# LEDs.net
KiCad netlist of a schematic drawn in Altium Designer
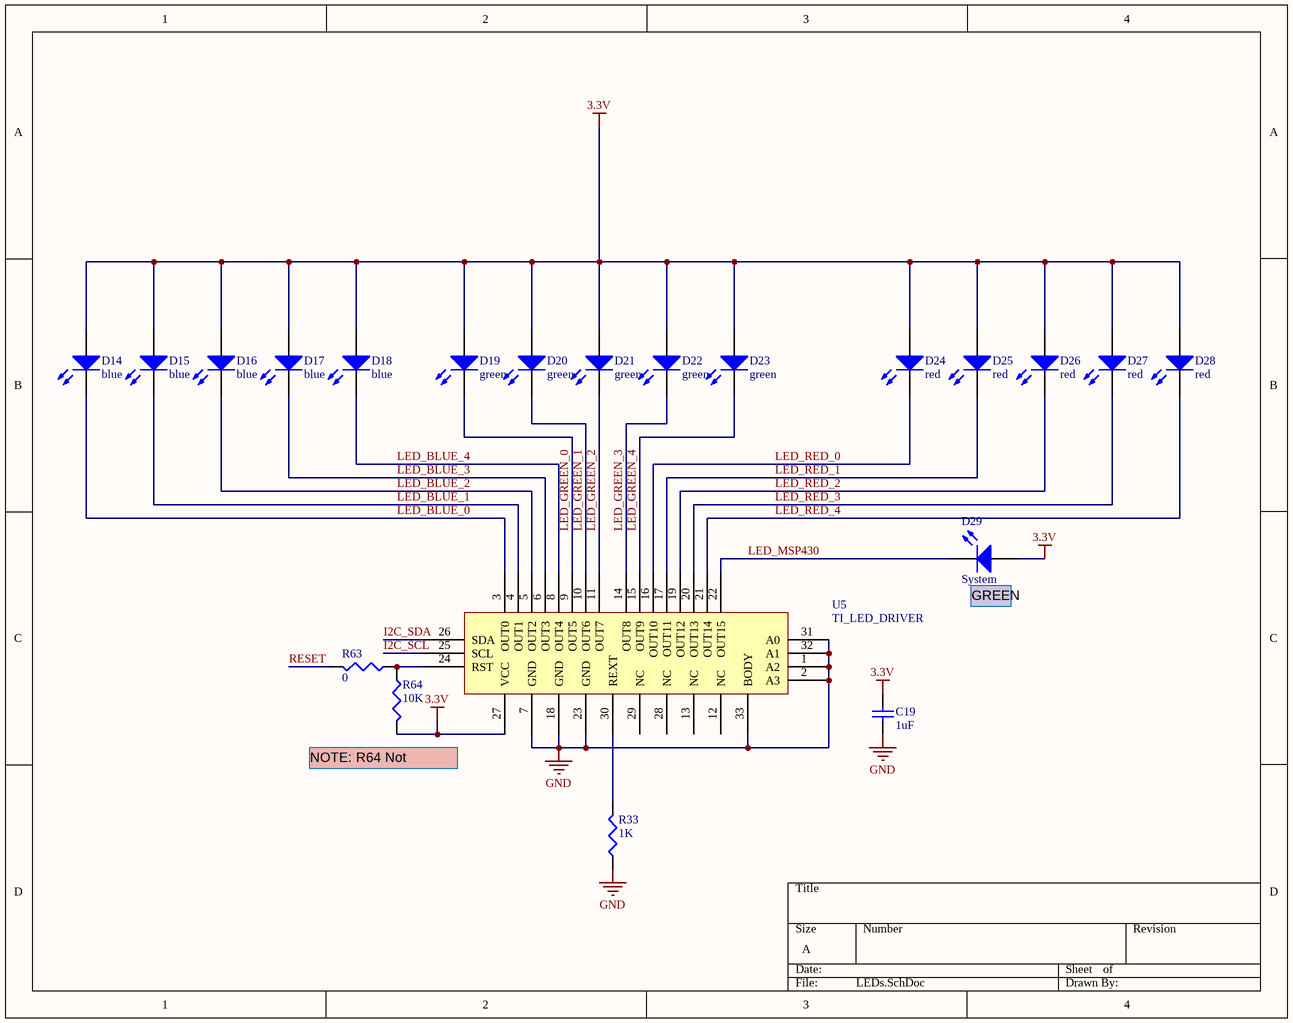
[diagram p0: LEDs.SchDoc]

(export (version "E")
  (design (tool "Eeschema 10.0.6"))
  (components
    (comp (ref "C19")
      (value "1uF")
      (footprint "CAPC1608L")
      (description "Capacitor (Semiconductor SIM Model)")
      (fields (field (name "Comment") "Cap Semi") (field (name "PUBLISHER") "Altium Limited"))
      (libsource (lib "Miscellaneous Devices") (part "Cap Semi"))
    )
    (comp (ref "D14") (value "blue") (footprint "SurfaceMount(603)") (libsource (lib "mrone") (part "LED")))
    (comp (ref "D15") (value "blue") (footprint "SurfaceMount(603)") (libsource (lib "mrone") (part "LED")))
    (comp (ref "D16") (value "blue") (footprint "SurfaceMount(603)") (libsource (lib "mrone") (part "LED")))
    (comp (ref "D17") (value "blue") (footprint "SurfaceMount(603)") (libsource (lib "mrone") (part "LED")))
    (comp (ref "D18") (value "blue") (footprint "SurfaceMount(603)") (libsource (lib "mrone") (part "LED")))
    (comp (ref "D19") (value "green") (footprint "SurfaceMount(603)") (libsource (lib "mrone") (part "LED")))
    (comp (ref "D20") (value "green") (footprint "SurfaceMount(603)") (libsource (lib "mrone") (part "LED")))
    (comp (ref "D21") (value "green") (footprint "SurfaceMount(603)") (libsource (lib "mrone") (part "LED")))
    (comp (ref "D22") (value "green") (footprint "SurfaceMount(603)") (libsource (lib "mrone") (part "LED")))
    (comp (ref "D23") (value "green") (footprint "SurfaceMount(603)") (libsource (lib "mrone") (part "LED")))
    (comp (ref "D24") (value "red") (footprint "SurfaceMount(603)") (libsource (lib "mrone") (part "LED")))
    (comp (ref "D25") (value "red") (footprint "SurfaceMount(603)") (libsource (lib "mrone") (part "LED")))
    (comp (ref "D26") (value "red") (footprint "SurfaceMount(603)") (libsource (lib "mrone") (part "LED")))
    (comp (ref "D27") (value "red") (footprint "SurfaceMount(603)") (libsource (lib "mrone") (part "LED")))
    (comp (ref "D28") (value "red") (footprint "SurfaceMount(603)") (libsource (lib "mrone") (part "LED")))
    (comp (ref "D29") (value "System") (footprint "SurfaceMount(603)") (libsource (lib "") (part "LED_1")))
    (comp (ref "R33")
      (value "1K")
      (footprint "RESC1608L")
      (description "Resistor")
      (fields (field (name "Comment") "Res3") (field (name "PUBLISHER") "Altium Limited"))
      (libsource (lib "Miscellaneous Devices") (part "Res3"))
    )
    (comp (ref "R63")
      (value "0")
      (footprint "RESC1608L")
      (description "Resistor")
      (fields (field (name "Comment") "Res3") (field (name "PUBLISHER") "Altium Limited"))
      (libsource (lib "Miscellaneous Devices") (part "Res3"))
    )
    (comp (ref "R64")
      (value "10K")
      (footprint "RESC1608L")
      (description "Resistor")
      (fields (field (name "Comment") "Res3") (field (name "PUBLISHER") "Altium Limited"))
      (libsource (lib "Miscellaneous Devices") (part "Res3"))
    )
    (comp (ref "U5")
      (value "TI_LED_DRIVER")
      (footprint "QFN32-LEDTLC59116")
      (libsource (lib "mrone") (part "TLC59116LEDDRIVER"))
    )
  )
  (nets
    (net (code "1") (name "/I2C_SCL") (class "Default")
      (node (ref "U5") (pin "25") (pinfunction "SCL_25") (pintype "passive"))
    )
    (net (code "2") (name "/I2C_SDA") (class "Default")
      (node (ref "U5") (pin "26") (pinfunction "SDA_26") (pintype "passive"))
    )
    (net (code "3") (name "/LED_BLUE_0") (class "Default")
      (node (ref "D14") (pin "2") (pinfunction "K_2") (pintype "passive"))
      (node (ref "U5") (pin "3") (pinfunction "OUT0_3") (pintype "passive"))
    )
    (net (code "4") (name "/LED_BLUE_1") (class "Default")
      (node (ref "D15") (pin "2") (pinfunction "K_2") (pintype "passive"))
      (node (ref "U5") (pin "4") (pinfunction "OUT1_4") (pintype "passive"))
    )
    (net (code "5") (name "/LED_BLUE_2") (class "Default")
      (node (ref "D16") (pin "2") (pinfunction "K_2") (pintype "passive"))
      (node (ref "U5") (pin "5") (pinfunction "OUT2_5") (pintype "passive"))
    )
    (net (code "6") (name "/LED_BLUE_3") (class "Default")
      (node (ref "D17") (pin "2") (pinfunction "K_2") (pintype "passive"))
      (node (ref "U5") (pin "6") (pinfunction "OUT3_6") (pintype "passive"))
    )
    (net (code "7") (name "/LED_BLUE_4") (class "Default")
      (node (ref "D18") (pin "2") (pinfunction "K_2") (pintype "passive"))
      (node (ref "U5") (pin "8") (pinfunction "OUT4_8") (pintype "passive"))
    )
    (net (code "8") (name "/LED_GREEN_0") (class "Default")
      (node (ref "D19") (pin "2") (pinfunction "K_2") (pintype "passive"))
      (node (ref "U5") (pin "9") (pinfunction "OUT5_9") (pintype "passive"))
    )
    (net (code "9") (name "/LED_GREEN_1") (class "Default")
      (node (ref "D20") (pin "2") (pinfunction "K_2") (pintype "passive"))
      (node (ref "U5") (pin "10") (pinfunction "OUT6_10") (pintype "passive"))
    )
    (net (code "10") (name "/LED_GREEN_2") (class "Default")
      (node (ref "D21") (pin "2") (pinfunction "K_2") (pintype "passive"))
      (node (ref "U5") (pin "11") (pinfunction "OUT7_11") (pintype "passive"))
    )
    (net (code "11") (name "/LED_GREEN_3") (class "Default")
      (node (ref "D22") (pin "2") (pinfunction "K_2") (pintype "passive"))
      (node (ref "U5") (pin "14") (pinfunction "OUT8_14") (pintype "passive"))
    )
    (net (code "12") (name "/LED_GREEN_4") (class "Default")
      (node (ref "D23") (pin "2") (pinfunction "K_2") (pintype "passive"))
      (node (ref "U5") (pin "15") (pinfunction "OUT9_15") (pintype "passive"))
    )
    (net (code "13") (name "/LED_MSP430") (class "Default")
      (node (ref "D29") (pin "2") (pinfunction "K_2") (pintype "passive"))
      (node (ref "U5") (pin "22") (pinfunction "OUT15_22") (pintype "passive"))
    )
    (net (code "14") (name "/LED_RED_0") (class "Default")
      (node (ref "D24") (pin "2") (pinfunction "K_2") (pintype "passive"))
      (node (ref "U5") (pin "16") (pinfunction "OUT10_16") (pintype "passive"))
    )
    (net (code "15") (name "/LED_RED_1") (class "Default")
      (node (ref "D25") (pin "2") (pinfunction "K_2") (pintype "passive"))
      (node (ref "U5") (pin "17") (pinfunction "OUT11_17") (pintype "passive"))
    )
    (net (code "16") (name "/LED_RED_2") (class "Default")
      (node (ref "D26") (pin "2") (pinfunction "K_2") (pintype "passive"))
      (node (ref "U5") (pin "19") (pinfunction "OUT12_19") (pintype "passive"))
    )
    (net (code "17") (name "/LED_RED_3") (class "Default")
      (node (ref "D27") (pin "2") (pinfunction "K_2") (pintype "passive"))
      (node (ref "U5") (pin "20") (pinfunction "OUT13_20") (pintype "passive"))
    )
    (net (code "18") (name "/LED_RED_4") (class "Default")
      (node (ref "D28") (pin "2") (pinfunction "K_2") (pintype "passive"))
      (node (ref "U5") (pin "21") (pinfunction "OUT14_21") (pintype "passive"))
    )
    (net (code "19") (name "/RESET") (class "Default")
      (node (ref "R63") (pin "2") (pinfunction "2_2") (pintype "passive"))
    )
    (net (code "20") (name "3.3V") (class "Default")
      (node (ref "C19") (pin "2") (pinfunction "2_2") (pintype "passive"))
      (node (ref "D14") (pin "1") (pinfunction "A_1") (pintype "passive"))
      (node (ref "D15") (pin "1") (pinfunction "A_1") (pintype "passive"))
      (node (ref "D16") (pin "1") (pinfunction "A_1") (pintype "passive"))
      (node (ref "D17") (pin "1") (pinfunction "A_1") (pintype "passive"))
      (node (ref "D18") (pin "1") (pinfunction "A_1") (pintype "passive"))
      (node (ref "D19") (pin "1") (pinfunction "A_1") (pintype "passive"))
      (node (ref "D20") (pin "1") (pinfunction "A_1") (pintype "passive"))
      (node (ref "D21") (pin "1") (pinfunction "A_1") (pintype "passive"))
      (node (ref "D22") (pin "1") (pinfunction "A_1") (pintype "passive"))
      (node (ref "D23") (pin "1") (pinfunction "A_1") (pintype "passive"))
      (node (ref "D24") (pin "1") (pinfunction "A_1") (pintype "passive"))
      (node (ref "D25") (pin "1") (pinfunction "A_1") (pintype "passive"))
      (node (ref "D26") (pin "1") (pinfunction "A_1") (pintype "passive"))
      (node (ref "D27") (pin "1") (pinfunction "A_1") (pintype "passive"))
      (node (ref "D28") (pin "1") (pinfunction "A_1") (pintype "passive"))
      (node (ref "D29") (pin "1") (pinfunction "A_1") (pintype "passive"))
      (node (ref "R64") (pin "2") (pinfunction "2_2") (pintype "passive"))
      (node (ref "U5") (pin "27") (pinfunction "VCC_27") (pintype "passive"))
    )
    (net (code "21") (name "GND") (class "Default")
      (node (ref "C19") (pin "1") (pinfunction "1_1") (pintype "passive"))
      (node (ref "R33") (pin "1") (pinfunction "1_1") (pintype "passive"))
      (node (ref "U5") (pin "1") (pinfunction "A2_1") (pintype "passive"))
      (node (ref "U5") (pin "18") (pinfunction "GND_18") (pintype "passive"))
      (node (ref "U5") (pin "2") (pinfunction "A3_2") (pintype "passive"))
      (node (ref "U5") (pin "23") (pinfunction "GND_23") (pintype "passive"))
      (node (ref "U5") (pin "31") (pinfunction "A0_31") (pintype "passive"))
      (node (ref "U5") (pin "32") (pinfunction "A1_32") (pintype "passive"))
      (node (ref "U5") (pin "33") (pinfunction "BODY_33") (pintype "passive"))
      (node (ref "U5") (pin "7") (pinfunction "GND_7") (pintype "passive"))
    )
    (net (code "22") (name "Net-(U5-REXT)") (class "Default")
      (node (ref "R33") (pin "2") (pinfunction "2_2") (pintype "passive"))
      (node (ref "U5") (pin "30") (pinfunction "REXT_30") (pintype "passive"))
    )
    (net (code "23") (name "Net-(U5-RST)") (class "Default")
      (node (ref "R63") (pin "1") (pinfunction "1_1") (pintype "passive"))
      (node (ref "R64") (pin "1") (pinfunction "1_1") (pintype "passive"))
      (node (ref "U5") (pin "24") (pinfunction "RST_24") (pintype "passive"))
    )
    (net (code "24") (name "unconnected-(U5-NC-Pad12)") (class "Default")
      (node (ref "U5") (pin "12") (pinfunction "NC_12") (pintype "passive"))
    )
    (net (code "25") (name "unconnected-(U5-NC-Pad13)") (class "Default")
      (node (ref "U5") (pin "13") (pinfunction "NC_13") (pintype "passive"))
    )
    (net (code "26") (name "unconnected-(U5-NC-Pad28)") (class "Default")
      (node (ref "U5") (pin "28") (pinfunction "NC_28") (pintype "passive"))
    )
    (net (code "27") (name "unconnected-(U5-NC-Pad29)") (class "Default")
      (node (ref "U5") (pin "29") (pinfunction "NC_29") (pintype "passive"))
    )
  )
)
